# 15.net
KiCad netlist of a schematic drawn in EAGLE
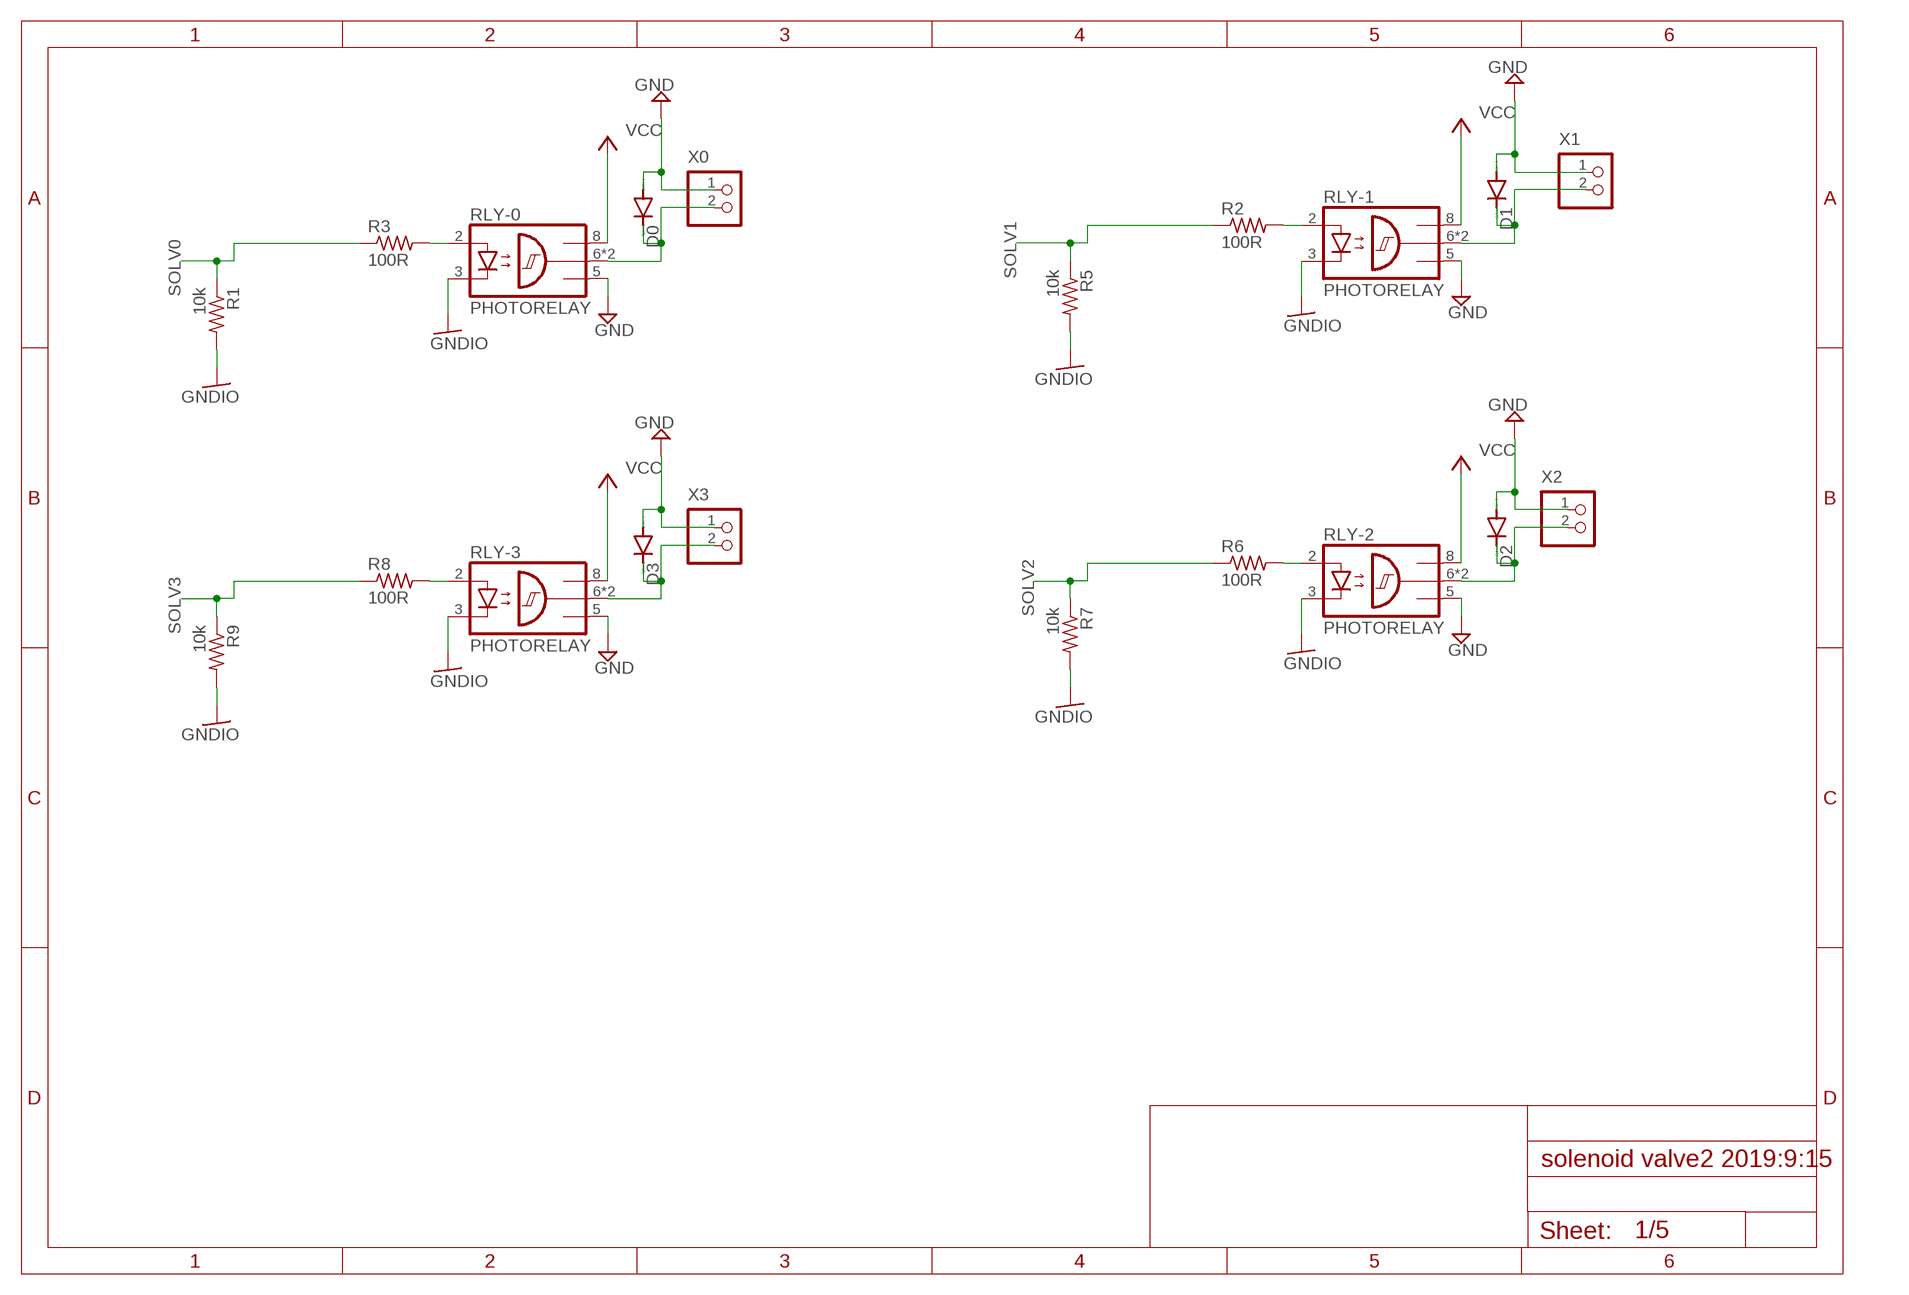
[diagram p0: schematic, sheet 1]
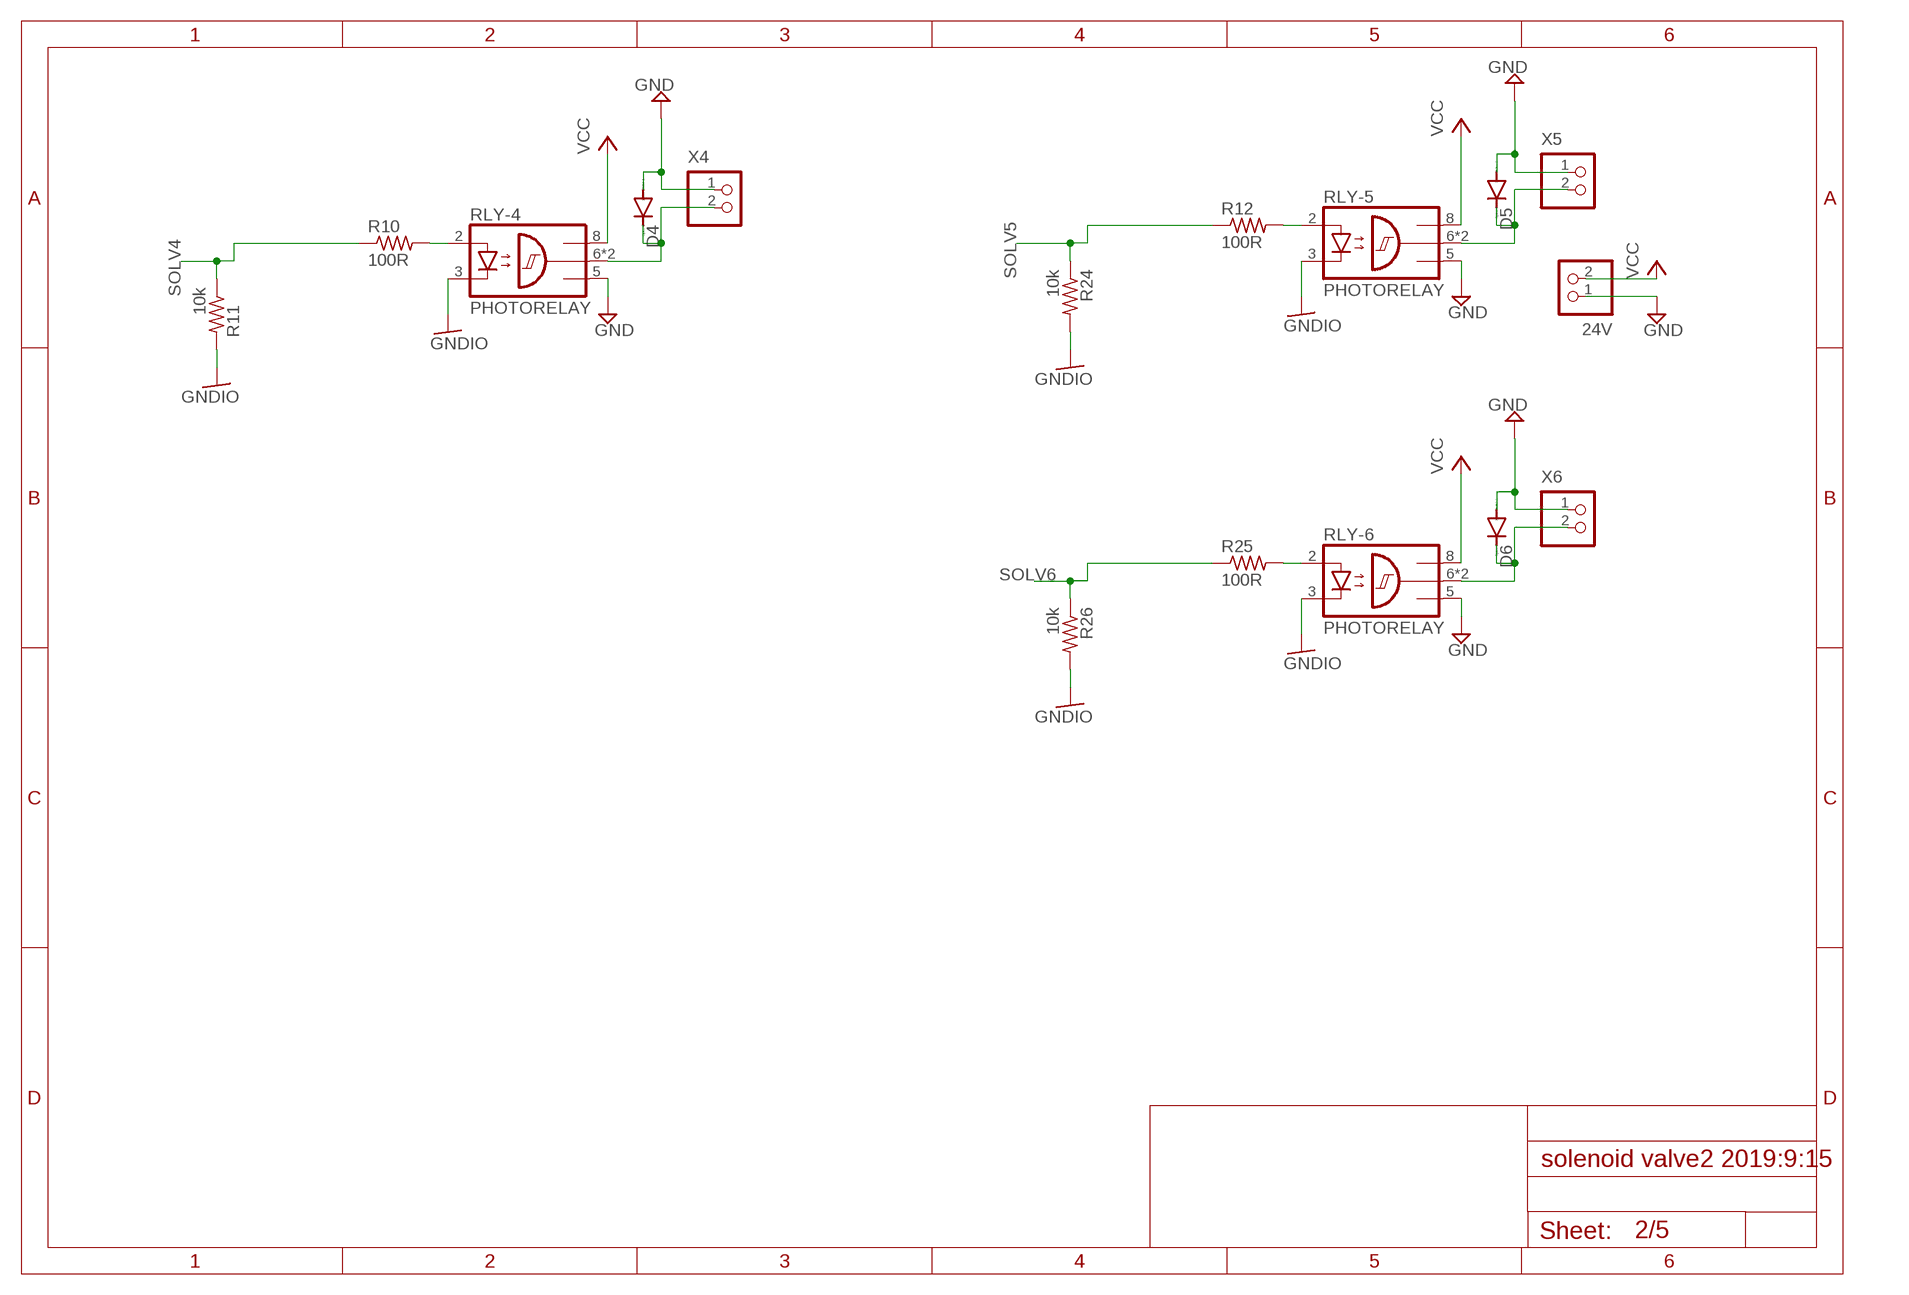
[diagram p1: schematic, sheet 2]
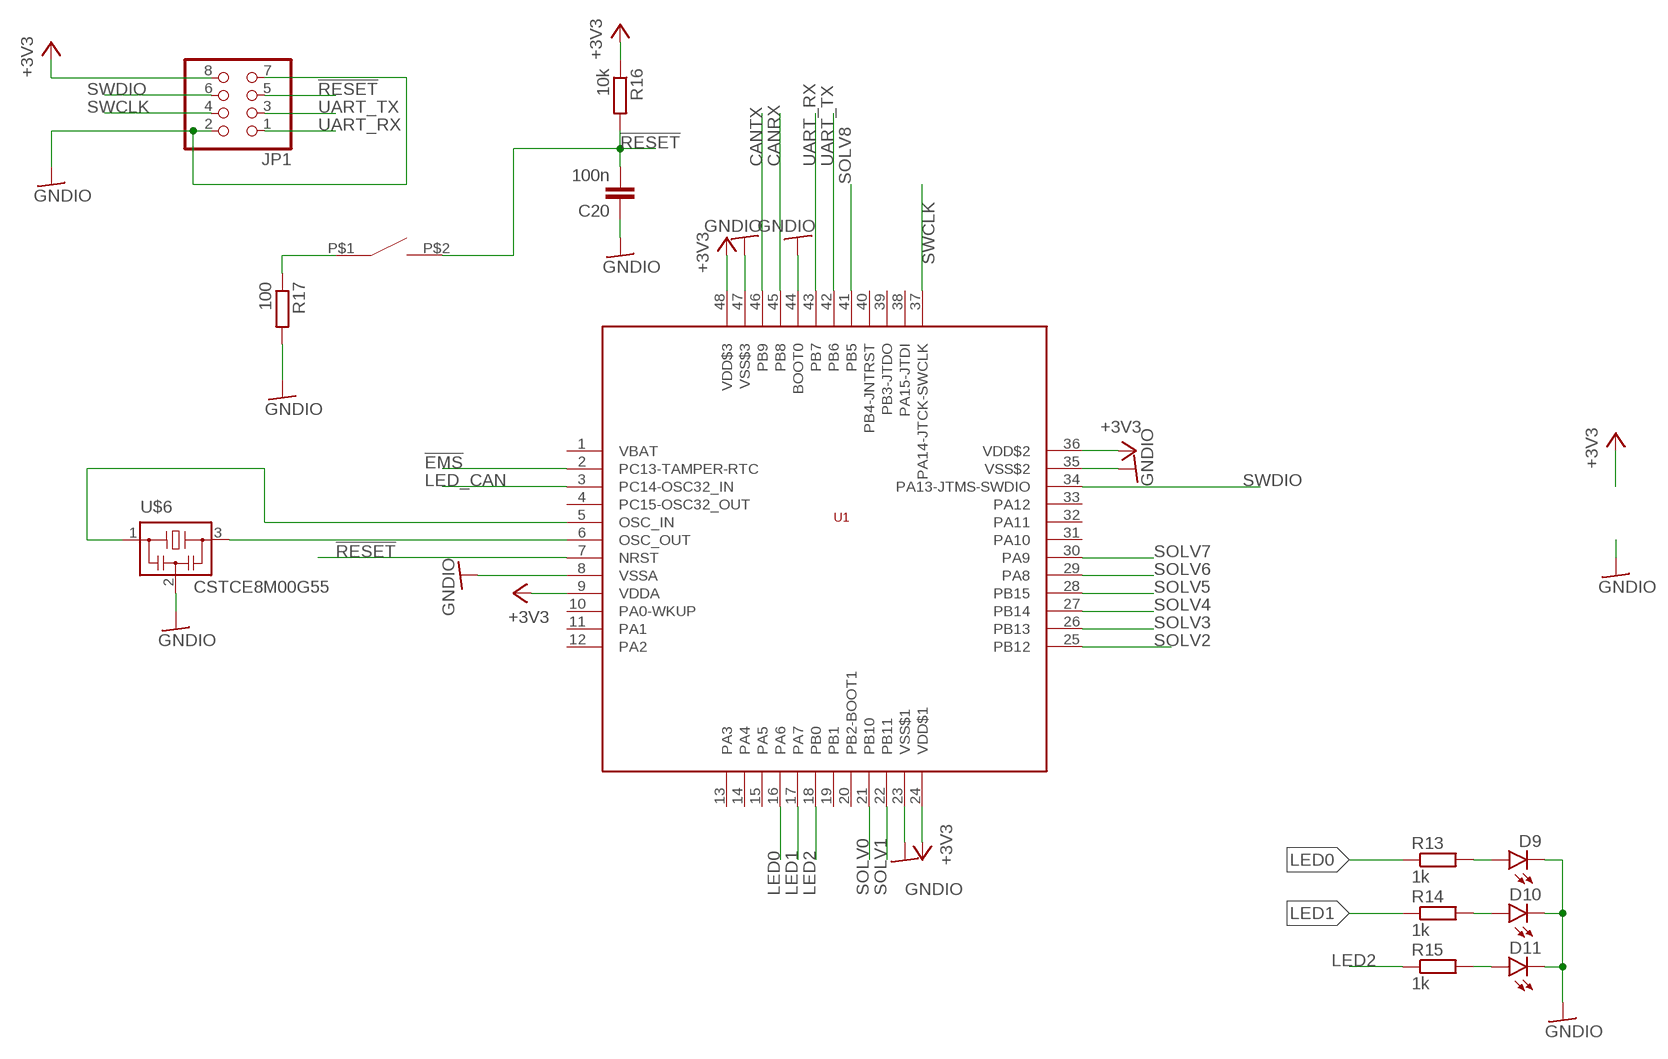
[diagram p2: schematic, sheet 3]
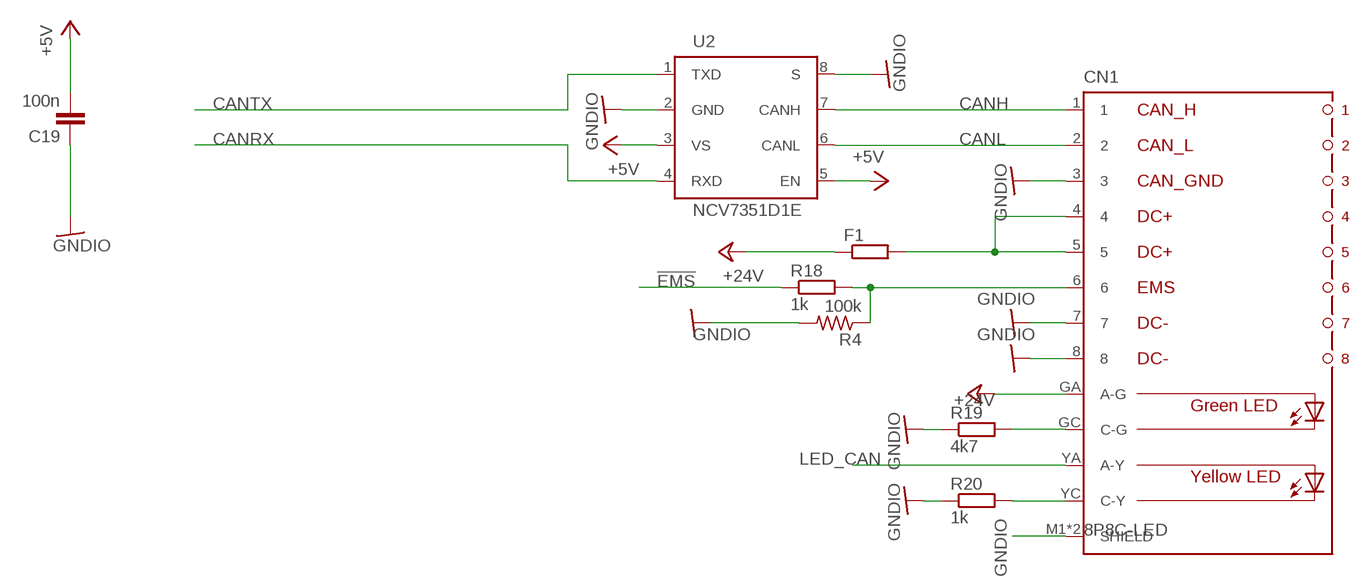
[diagram p3: schematic, sheet 4]
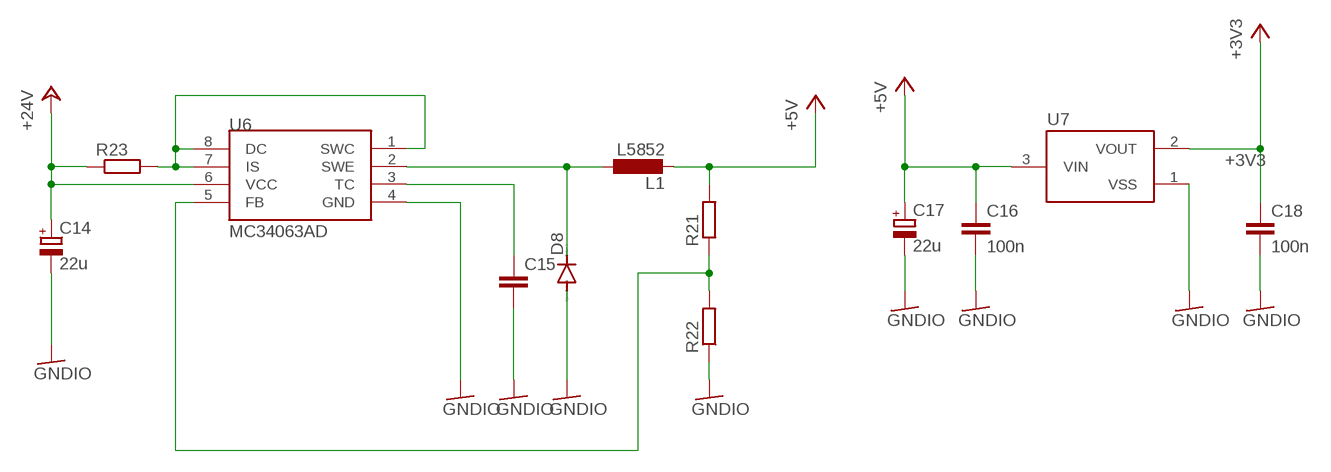
[diagram p4: schematic, sheet 5]

(export (version "E")
  (design (tool "Eeschema 10.0.6"))
  (components
    (comp (ref "C19")
      (value "100n")
      (footprint "eagle-import:C0603")
      (libsource (lib "eagle-import") (part "C-EUC0603"))
    )
    (comp (ref "CN1")
      (value "8P8C-LED")
      (footprint "eagle-import:8P8C-LED")
      (libsource (lib "eagle-import") (part "8P8C-LED"))
    )
    (comp (ref "F1")
      (value "R-EU_R1206")
      (footprint "eagle-import:R1206")
      (libsource (lib "eagle-import") (part "rcl_334_R-EU_R1206"))
    )
    (comp (ref "R4")
      (value "100k")
      (footprint "eagle-import:R0603")
      (libsource (lib "eagle-import") (part "R-US_R0603"))
    )
    (comp (ref "R18")
      (value "1k")
      (footprint "eagle-import:R0603")
      (libsource (lib "eagle-import") (part "rcl_334_R-EU_R0603"))
    )
    (comp (ref "R19")
      (value "4k7")
      (footprint "eagle-import:R0603")
      (libsource (lib "eagle-import") (part "rcl_334_R-EU_R0603"))
    )
    (comp (ref "R20")
      (value "1k")
      (footprint "eagle-import:R0603")
      (libsource (lib "eagle-import") (part "rcl_334_R-EU_R0603"))
    )
    (comp (ref "U2")
      (value "NCV7351D1E")
      (footprint "eagle-import:SO08")
      (libsource (lib "eagle-import") (part "NCV7351D1E"))
    )
    (comp (ref "C14")
      (value "22u")
      (footprint "eagle-import:E2-5")
      (libsource (lib "eagle-import") (part "CPOL-EUE2-5"))
    )
    (comp (ref "C15")
      (value "C-EUC0603")
      (footprint "eagle-import:C0603")
      (libsource (lib "eagle-import") (part "rcl_334_C-EUC0603"))
    )
    (comp (ref "C16")
      (value "100n")
      (footprint "eagle-import:C0603")
      (libsource (lib "eagle-import") (part "C-EUC0603"))
    )
    (comp (ref "C17")
      (value "22u")
      (footprint "eagle-import:E2-5")
      (libsource (lib "eagle-import") (part "CPOL-EUE2-5"))
    )
    (comp (ref "C18")
      (value "100n")
      (footprint "eagle-import:C0603")
      (libsource (lib "eagle-import") (part "C-EUC0603"))
    )
    (comp (ref "D8")
      (value "DIODE-SOD123")
      (footprint "eagle-import:SOD123")
      (libsource (lib "eagle-import") (part "DIODE-SOD123"))
    )
    (comp (ref "L1")
      (value "L5852")
      (footprint "eagle-import:L5852")
      (libsource (lib "eagle-import") (part "L5852"))
    )
    (comp (ref "R21")
      (value "R-EU_R0603")
      (footprint "eagle-import:R0603")
      (libsource (lib "eagle-import") (part "rcl_334_R-EU_R0603"))
    )
    (comp (ref "R22")
      (value "R-EU_R0603")
      (footprint "eagle-import:R0603")
      (libsource (lib "eagle-import") (part "rcl_334_R-EU_R0603"))
    )
    (comp (ref "R23")
      (value "R-EU_R1206")
      (footprint "eagle-import:R1206")
      (libsource (lib "eagle-import") (part "rcl_334_R-EU_R1206"))
    )
    (comp (ref "U6")
      (value "MC34063AD")
      (footprint "eagle-import:SOIC8")
      (libsource (lib "eagle-import") (part "MC34063AD"))
    )
    (comp (ref "U7")
      (value "XC6206")
      (footprint "eagle-import:SOT95P240X110-3")
      (libsource (lib "eagle-import") (part "XC6206"))
    )
    (comp (ref "D0")
      (value "DIODE-SOD123")
      (footprint "eagle-import:SOD123")
      (libsource (lib "eagle-import") (part "DIODE-SOD123"))
    )
    (comp (ref "D1")
      (value "DIODE-SOD123")
      (footprint "eagle-import:SOD123")
      (libsource (lib "eagle-import") (part "DIODE-SOD123"))
    )
    (comp (ref "D2")
      (value "DIODE-SOD123")
      (footprint "eagle-import:SOD123")
      (libsource (lib "eagle-import") (part "DIODE-SOD123"))
    )
    (comp (ref "D3")
      (value "DIODE-SOD123")
      (footprint "eagle-import:SOD123")
      (libsource (lib "eagle-import") (part "DIODE-SOD123"))
    )
    (comp (ref "R1")
      (value "10k")
      (footprint "eagle-import:R0603")
      (libsource (lib "eagle-import") (part "R-US_R0603"))
    )
    (comp (ref "R2")
      (value "100R")
      (footprint "eagle-import:R0603")
      (libsource (lib "eagle-import") (part "R-US_R0603"))
    )
    (comp (ref "R3")
      (value "100R")
      (footprint "eagle-import:R0603")
      (libsource (lib "eagle-import") (part "R-US_R0603"))
    )
    (comp (ref "R5")
      (value "10k")
      (footprint "eagle-import:R0603")
      (libsource (lib "eagle-import") (part "R-US_R0603"))
    )
    (comp (ref "R6")
      (value "100R")
      (footprint "eagle-import:R0603")
      (libsource (lib "eagle-import") (part "R-US_R0603"))
    )
    (comp (ref "R7")
      (value "10k")
      (footprint "eagle-import:R0603")
      (libsource (lib "eagle-import") (part "R-US_R0603"))
    )
    (comp (ref "R8")
      (value "100R")
      (footprint "eagle-import:R0603")
      (libsource (lib "eagle-import") (part "R-US_R0603"))
    )
    (comp (ref "R9")
      (value "10k")
      (footprint "eagle-import:R0603")
      (libsource (lib "eagle-import") (part "R-US_R0603"))
    )
    (comp (ref "RLY-0")
      (value "PHOTORELAY")
      (footprint "eagle-import:SOP254P1016X385-8")
      (libsource (lib "eagle-import") (part "PHOTORELAY"))
    )
    (comp (ref "RLY-1")
      (value "PHOTORELAY")
      (footprint "eagle-import:SOP254P1016X385-8")
      (libsource (lib "eagle-import") (part "PHOTORELAY"))
    )
    (comp (ref "RLY-2")
      (value "PHOTORELAY")
      (footprint "eagle-import:SOP254P1016X385-8")
      (libsource (lib "eagle-import") (part "PHOTORELAY"))
    )
    (comp (ref "RLY-3")
      (value "PHOTORELAY")
      (footprint "eagle-import:SOP254P1016X385-8")
      (libsource (lib "eagle-import") (part "PHOTORELAY"))
    )
    (comp (ref "X0")
      (value "S2B-XASK-1")
      (footprint "eagle-import:S2B-XASK-1")
      (libsource (lib "eagle-import") (part "S2B-XASK-1"))
    )
    (comp (ref "X1")
      (value "S2B-XASK-1")
      (footprint "eagle-import:S2B-XASK-1")
      (libsource (lib "eagle-import") (part "S2B-XASK-1"))
    )
    (comp (ref "X2")
      (value "S2B-XASK-1")
      (footprint "eagle-import:S2B-XASK-1")
      (libsource (lib "eagle-import") (part "S2B-XASK-1"))
    )
    (comp (ref "X3")
      (value "S2B-XASK-1")
      (footprint "eagle-import:S2B-XASK-1")
      (libsource (lib "eagle-import") (part "S2B-XASK-1"))
    )
    (comp (ref "24V")
      (value "S2B-XASK-1")
      (footprint "eagle-import:S2B-XASK-1")
      (libsource (lib "eagle-import") (part "S2B-XASK-1"))
    )
    (comp (ref "D4")
      (value "DIODE-SOD123")
      (footprint "eagle-import:SOD123")
      (libsource (lib "eagle-import") (part "DIODE-SOD123"))
    )
    (comp (ref "D5")
      (value "DIODE-SOD123")
      (footprint "eagle-import:SOD123")
      (libsource (lib "eagle-import") (part "DIODE-SOD123"))
    )
    (comp (ref "D6")
      (value "DIODE-SOD123")
      (footprint "eagle-import:SOD123")
      (libsource (lib "eagle-import") (part "DIODE-SOD123"))
    )
    (comp (ref "R10")
      (value "100R")
      (footprint "eagle-import:R0603")
      (libsource (lib "eagle-import") (part "R-US_R0603"))
    )
    (comp (ref "R11")
      (value "10k")
      (footprint "eagle-import:R0603")
      (libsource (lib "eagle-import") (part "R-US_R0603"))
    )
    (comp (ref "R12")
      (value "100R")
      (footprint "eagle-import:R0603")
      (libsource (lib "eagle-import") (part "R-US_R0603"))
    )
    (comp (ref "R24")
      (value "10k")
      (footprint "eagle-import:R0603")
      (libsource (lib "eagle-import") (part "R-US_R0603"))
    )
    (comp (ref "R25")
      (value "100R")
      (footprint "eagle-import:R0603")
      (libsource (lib "eagle-import") (part "R-US_R0603"))
    )
    (comp (ref "R26")
      (value "10k")
      (footprint "eagle-import:R0603")
      (libsource (lib "eagle-import") (part "R-US_R0603"))
    )
    (comp (ref "RLY-4")
      (value "PHOTORELAY")
      (footprint "eagle-import:SOP254P1016X385-8")
      (libsource (lib "eagle-import") (part "PHOTORELAY"))
    )
    (comp (ref "RLY-5")
      (value "PHOTORELAY")
      (footprint "eagle-import:SOP254P1016X385-8")
      (libsource (lib "eagle-import") (part "PHOTORELAY"))
    )
    (comp (ref "RLY-6")
      (value "PHOTORELAY")
      (footprint "eagle-import:SOP254P1016X385-8")
      (libsource (lib "eagle-import") (part "PHOTORELAY"))
    )
    (comp (ref "X4")
      (value "S2B-XASK-1")
      (footprint "eagle-import:S2B-XASK-1")
      (libsource (lib "eagle-import") (part "S2B-XASK-1"))
    )
    (comp (ref "X5")
      (value "S2B-XASK-1")
      (footprint "eagle-import:S2B-XASK-1")
      (libsource (lib "eagle-import") (part "S2B-XASK-1"))
    )
    (comp (ref "X6")
      (value "S2B-XASK-1")
      (footprint "eagle-import:S2B-XASK-1")
      (libsource (lib "eagle-import") (part "S2B-XASK-1"))
    )
    (comp (ref "C20")
      (value "100n")
      (footprint "eagle-import:C0603")
      (libsource (lib "eagle-import") (part "C-EUC0603"))
    )
    (comp (ref "D9")
      (value "LEDCHIPLED_0805")
      (footprint "eagle-import:CHIPLED_0805")
      (libsource (lib "eagle-import") (part "LEDCHIPLED_0805"))
    )
    (comp (ref "D10")
      (value "LEDCHIPLED_0805")
      (footprint "eagle-import:CHIPLED_0805")
      (libsource (lib "eagle-import") (part "LEDCHIPLED_0805"))
    )
    (comp (ref "D11")
      (value "LEDCHIPLED_0805")
      (footprint "eagle-import:CHIPLED_0805")
      (libsource (lib "eagle-import") (part "LEDCHIPLED_0805"))
    )
    (comp (ref "JP1")
      (value "PINHD-2X4/90")
      (footprint "eagle-import:2X04_90")
      (libsource (lib "eagle-import") (part "PINHD-2X4/90"))
    )
    (comp (ref "R13")
      (value "1k")
      (footprint "eagle-import:R0603")
      (libsource (lib "eagle-import") (part "R-EU_R0603"))
    )
    (comp (ref "R14")
      (value "1k")
      (footprint "eagle-import:R0603")
      (libsource (lib "eagle-import") (part "R-EU_R0603"))
    )
    (comp (ref "R15")
      (value "1k")
      (footprint "eagle-import:R0603")
      (libsource (lib "eagle-import") (part "R-EU_R0603"))
    )
    (comp (ref "R16")
      (value "10k")
      (footprint "eagle-import:R0603")
      (libsource (lib "eagle-import") (part "R-EU_R0603"))
    )
    (comp (ref "R17")
      (value "100")
      (footprint "eagle-import:R0603")
      (libsource (lib "eagle-import") (part "R-EU_R0603"))
    )
    (comp (ref "SW1")
      (value "SWITCH_TACTILETOP")
      (footprint "eagle-import:SWITCH_TACTILE_3X6")
      (libsource (lib "eagle-import") (part "SWITCH_TACTILETOP"))
    )
    (comp (ref "U$6")
      (value "CSTCE8M00G55")
      (footprint "eagle-import:CSTCE8M00G55")
      (libsource (lib "eagle-import") (part "CSTCE8M00G55"))
    )
    (comp (ref "U1")
      (value "STM32F103C8")
      (footprint "eagle-import:LQFP48")
      (libsource (lib "eagle-import") (part "STM32F103C8"))
    )
  )
  (nets
    (net (code "1") (name "+3V3") (class "Default")
      (node (ref "C18") (pin "1") (pinfunction "1_1") (pintype "passive"))
      (node (ref "JP1") (pin "8") (pinfunction "8_8") (pintype "passive"))
      (node (ref "R16") (pin "1") (pinfunction "1_1") (pintype "passive"))
      (node (ref "U1") (pin "24") (pinfunction "VDD$1_24") (pintype "passive"))
      (node (ref "U1") (pin "36") (pinfunction "VDD$2_36") (pintype "passive"))
      (node (ref "U1") (pin "48") (pinfunction "VDD$3_48") (pintype "passive"))
      (node (ref "U1") (pin "9") (pinfunction "VDDA_9") (pintype "bidirectional"))
      (node (ref "U7") (pin "2") (pinfunction "VOUT_2") (pintype "bidirectional"))
    )
    (net (code "2") (name "+5V") (class "Default")
      (node (ref "C16") (pin "1") (pinfunction "1_1") (pintype "passive"))
      (node (ref "C17") (pin "+") (pinfunction "+_+") (pintype "passive"))
      (node (ref "C19") (pin "2") (pinfunction "2_2") (pintype "passive"))
      (node (ref "L1") (pin "P$2") (pinfunction "2_P$2") (pintype "passive"))
      (node (ref "R21") (pin "2") (pinfunction "2_2") (pintype "passive"))
      (node (ref "U2") (pin "3") (pinfunction "VS_3") (pintype "power_in"))
      (node (ref "U2") (pin "5") (pinfunction "EN_5") (pintype "input"))
      (node (ref "U7") (pin "3") (pinfunction "VIN_3") (pintype "bidirectional"))
    )
    (net (code "3") (name "+24V") (class "Default")
      (node (ref "C14") (pin "+") (pinfunction "+_+") (pintype "passive"))
      (node (ref "CN1") (pin "GA") (pinfunction "A-G_GA") (pintype "passive"))
      (node (ref "F1") (pin "1") (pinfunction "1_1") (pintype "passive"))
      (node (ref "R23") (pin "1") (pinfunction "1_1") (pintype "passive"))
      (node (ref "U6") (pin "6") (pinfunction "VCC_6") (pintype "passive"))
    )
    (net (code "4") (name "CANH") (class "Default")
      (node (ref "CN1") (pin "1") (pinfunction "1_1") (pintype "input"))
      (node (ref "U2") (pin "7") (pinfunction "CANH_7") (pintype "output"))
    )
    (net (code "5") (name "CANL") (class "Default")
      (node (ref "CN1") (pin "2") (pinfunction "2_2") (pintype "input"))
      (node (ref "U2") (pin "6") (pinfunction "CANL_6") (pintype "output"))
    )
    (net (code "6") (name "CANRX") (class "Default")
      (node (ref "U1") (pin "45") (pinfunction "PB8_45") (pintype "bidirectional"))
      (node (ref "U2") (pin "4") (pinfunction "RXD_4") (pintype "output"))
    )
    (net (code "7") (name "CANTX") (class "Default")
      (node (ref "U1") (pin "46") (pinfunction "PB9_46") (pintype "bidirectional"))
      (node (ref "U2") (pin "1") (pinfunction "TXD_1") (pintype "input"))
    )
    (net (code "8") (name "GND") (class "Default")
      (node (ref "24V") (pin "1") (pinfunction "1_1") (pintype "passive"))
      (node (ref "D0") (pin "A") (pinfunction "A_A") (pintype "passive"))
      (node (ref "D1") (pin "A") (pinfunction "A_A") (pintype "passive"))
      (node (ref "D2") (pin "A") (pinfunction "A_A") (pintype "passive"))
      (node (ref "D3") (pin "A") (pinfunction "A_A") (pintype "passive"))
      (node (ref "D4") (pin "A") (pinfunction "A_A") (pintype "passive"))
      (node (ref "D5") (pin "A") (pinfunction "A_A") (pintype "passive"))
      (node (ref "D6") (pin "A") (pinfunction "A_A") (pintype "passive"))
      (node (ref "RLY-0") (pin "5") (pinfunction "GND_5") (pintype "passive"))
      (node (ref "RLY-1") (pin "5") (pinfunction "GND_5") (pintype "passive"))
      (node (ref "RLY-2") (pin "5") (pinfunction "GND_5") (pintype "passive"))
      (node (ref "RLY-3") (pin "5") (pinfunction "GND_5") (pintype "passive"))
      (node (ref "RLY-4") (pin "5") (pinfunction "GND_5") (pintype "passive"))
      (node (ref "RLY-5") (pin "5") (pinfunction "GND_5") (pintype "passive"))
      (node (ref "RLY-6") (pin "5") (pinfunction "GND_5") (pintype "passive"))
      (node (ref "X0") (pin "1") (pinfunction "1_1") (pintype "passive"))
      (node (ref "X1") (pin "1") (pinfunction "1_1") (pintype "passive"))
      (node (ref "X2") (pin "1") (pinfunction "1_1") (pintype "passive"))
      (node (ref "X3") (pin "1") (pinfunction "1_1") (pintype "passive"))
      (node (ref "X4") (pin "1") (pinfunction "1_1") (pintype "passive"))
      (node (ref "X5") (pin "1") (pinfunction "1_1") (pintype "passive"))
      (node (ref "X6") (pin "1") (pinfunction "1_1") (pintype "passive"))
    )
    (net (code "9") (name "GNDIO") (class "Default")
      (node (ref "C14") (pin "-") (pinfunction "-_-") (pintype "passive"))
      (node (ref "C15") (pin "2") (pinfunction "2_2") (pintype "passive"))
      (node (ref "C16") (pin "2") (pinfunction "2_2") (pintype "passive"))
      (node (ref "C17") (pin "-") (pinfunction "-_-") (pintype "passive"))
      (node (ref "C18") (pin "2") (pinfunction "2_2") (pintype "passive"))
      (node (ref "C19") (pin "1") (pinfunction "1_1") (pintype "passive"))
      (node (ref "C20") (pin "1") (pinfunction "1_1") (pintype "passive"))
      (node (ref "CN1") (pin "3") (pinfunction "3_3") (pintype "input"))
      (node (ref "CN1") (pin "7") (pinfunction "7_7") (pintype "input"))
      (node (ref "CN1") (pin "8") (pinfunction "8_8") (pintype "input"))
      (node (ref "CN1") (pin "M1") (pinfunction "SHIELD_M1") (pintype "passive"))
      (node (ref "CN1") (pin "M2") (pinfunction "SHIELD_M2") (pintype "passive"))
      (node (ref "D10") (pin "C") (pinfunction "C_C") (pintype "passive"))
      (node (ref "D11") (pin "C") (pinfunction "C_C") (pintype "passive"))
      (node (ref "D8") (pin "A") (pinfunction "A_A") (pintype "passive"))
      (node (ref "D9") (pin "C") (pinfunction "C_C") (pintype "passive"))
      (node (ref "JP1") (pin "2") (pinfunction "2_2") (pintype "passive"))
      (node (ref "JP1") (pin "7") (pinfunction "7_7") (pintype "passive"))
      (node (ref "R1") (pin "2") (pinfunction "2_2") (pintype "passive"))
      (node (ref "R11") (pin "2") (pinfunction "2_2") (pintype "passive"))
      (node (ref "R17") (pin "2") (pinfunction "2_2") (pintype "passive"))
      (node (ref "R19") (pin "1") (pinfunction "1_1") (pintype "passive"))
      (node (ref "R20") (pin "1") (pinfunction "1_1") (pintype "passive"))
      (node (ref "R22") (pin "1") (pinfunction "1_1") (pintype "passive"))
      (node (ref "R24") (pin "2") (pinfunction "2_2") (pintype "passive"))
      (node (ref "R26") (pin "2") (pinfunction "2_2") (pintype "passive"))
      (node (ref "R4") (pin "2") (pinfunction "2_2") (pintype "passive"))
      (node (ref "R5") (pin "2") (pinfunction "2_2") (pintype "passive"))
      (node (ref "R7") (pin "2") (pinfunction "2_2") (pintype "passive"))
      (node (ref "R9") (pin "2") (pinfunction "2_2") (pintype "passive"))
      (node (ref "RLY-0") (pin "3") (pinfunction "C_3") (pintype "passive"))
      (node (ref "RLY-1") (pin "3") (pinfunction "C_3") (pintype "passive"))
      (node (ref "RLY-2") (pin "3") (pinfunction "C_3") (pintype "passive"))
      (node (ref "RLY-3") (pin "3") (pinfunction "C_3") (pintype "passive"))
      (node (ref "RLY-4") (pin "3") (pinfunction "C_3") (pintype "passive"))
      (node (ref "RLY-5") (pin "3") (pinfunction "C_3") (pintype "passive"))
      (node (ref "RLY-6") (pin "3") (pinfunction "C_3") (pintype "passive"))
      (node (ref "U$6") (pin "2") (pinfunction "2_2") (pintype "passive"))
      (node (ref "U1") (pin "23") (pinfunction "VSS$1_23") (pintype "passive"))
      (node (ref "U1") (pin "35") (pinfunction "VSS$2_35") (pintype "passive"))
      (node (ref "U1") (pin "44") (pinfunction "BOOT0_44") (pintype "input"))
      (node (ref "U1") (pin "47") (pinfunction "VSS$3_47") (pintype "passive"))
      (node (ref "U1") (pin "8") (pinfunction "VSSA_8") (pintype "bidirectional"))
      (node (ref "U2") (pin "2") (pinfunction "GND_2") (pintype "power_in"))
      (node (ref "U2") (pin "8") (pinfunction "S_8") (pintype "input"))
      (node (ref "U6") (pin "4") (pinfunction "GND_4") (pintype "passive"))
      (node (ref "U7") (pin "1") (pinfunction "VSS_1") (pintype "bidirectional"))
    )
    (net (code "10") (name "LED0") (class "Default")
      (node (ref "R13") (pin "1") (pinfunction "1_1") (pintype "passive"))
      (node (ref "U1") (pin "16") (pinfunction "PA6_16") (pintype "bidirectional"))
    )
    (net (code "11") (name "LED1") (class "Default")
      (node (ref "R14") (pin "1") (pinfunction "1_1") (pintype "passive"))
      (node (ref "U1") (pin "17") (pinfunction "PA7_17") (pintype "bidirectional"))
    )
    (net (code "12") (name "LED2") (class "Default")
      (node (ref "R15") (pin "1") (pinfunction "1_1") (pintype "passive"))
      (node (ref "U1") (pin "18") (pinfunction "PB0_18") (pintype "bidirectional"))
    )
    (net (code "13") (name "LED_CAN") (class "Default")
      (node (ref "CN1") (pin "YA") (pinfunction "A-Y_YA") (pintype "passive"))
      (node (ref "U1") (pin "3") (pinfunction "PC14-OSC32_IN_3") (pintype "bidirectional"))
    )
    (net (code "14") (name "Net-(CN1-C-G)") (class "Default")
      (node (ref "CN1") (pin "GC") (pinfunction "C-G_GC") (pintype "passive"))
      (node (ref "R19") (pin "2") (pinfunction "2_2") (pintype "passive"))
    )
    (net (code "15") (name "Net-(CN1-C-Y)") (class "Default")
      (node (ref "CN1") (pin "YC") (pinfunction "C-Y_YC") (pintype "passive"))
      (node (ref "R20") (pin "2") (pinfunction "2_2") (pintype "passive"))
    )
    (net (code "16") (name "Net-(CN1-Pad4)") (class "Default")
      (node (ref "CN1") (pin "4") (pinfunction "4_4") (pintype "input"))
      (node (ref "CN1") (pin "5") (pinfunction "5_5") (pintype "input"))
      (node (ref "F1") (pin "2") (pinfunction "2_2") (pintype "passive"))
    )
    (net (code "17") (name "Net-(CN1-Pad6)") (class "Default")
      (node (ref "CN1") (pin "6") (pinfunction "6_6") (pintype "input"))
      (node (ref "R18") (pin "2") (pinfunction "2_2") (pintype "passive"))
      (node (ref "R4") (pin "1") (pinfunction "1_1") (pintype "passive"))
    )
    (net (code "18") (name "Net-(D0-PadC)") (class "Default")
      (node (ref "D0") (pin "C") (pinfunction "C_C") (pintype "passive"))
      (node (ref "RLY-0") (pin "6") (pinfunction "OUT_6") (pintype "passive"))
      (node (ref "RLY-0") (pin "7") (pinfunction "OUT_7") (pintype "passive"))
      (node (ref "X0") (pin "2") (pinfunction "2_2") (pintype "passive"))
    )
    (net (code "19") (name "Net-(D1-PadC)") (class "Default")
      (node (ref "D1") (pin "C") (pinfunction "C_C") (pintype "passive"))
      (node (ref "RLY-1") (pin "6") (pinfunction "OUT_6") (pintype "passive"))
      (node (ref "RLY-1") (pin "7") (pinfunction "OUT_7") (pintype "passive"))
      (node (ref "X1") (pin "2") (pinfunction "2_2") (pintype "passive"))
    )
    (net (code "20") (name "Net-(D2-PadC)") (class "Default")
      (node (ref "D2") (pin "C") (pinfunction "C_C") (pintype "passive"))
      (node (ref "RLY-2") (pin "6") (pinfunction "OUT_6") (pintype "passive"))
      (node (ref "RLY-2") (pin "7") (pinfunction "OUT_7") (pintype "passive"))
      (node (ref "X2") (pin "2") (pinfunction "2_2") (pintype "passive"))
    )
    (net (code "21") (name "Net-(D3-PadC)") (class "Default")
      (node (ref "D3") (pin "C") (pinfunction "C_C") (pintype "passive"))
      (node (ref "RLY-3") (pin "6") (pinfunction "OUT_6") (pintype "passive"))
      (node (ref "RLY-3") (pin "7") (pinfunction "OUT_7") (pintype "passive"))
      (node (ref "X3") (pin "2") (pinfunction "2_2") (pintype "passive"))
    )
    (net (code "22") (name "Net-(D4-PadC)") (class "Default")
      (node (ref "D4") (pin "C") (pinfunction "C_C") (pintype "passive"))
      (node (ref "RLY-4") (pin "6") (pinfunction "OUT_6") (pintype "passive"))
      (node (ref "RLY-4") (pin "7") (pinfunction "OUT_7") (pintype "passive"))
      (node (ref "X4") (pin "2") (pinfunction "2_2") (pintype "passive"))
    )
    (net (code "23") (name "Net-(D5-PadC)") (class "Default")
      (node (ref "D5") (pin "C") (pinfunction "C_C") (pintype "passive"))
      (node (ref "RLY-5") (pin "6") (pinfunction "OUT_6") (pintype "passive"))
      (node (ref "RLY-5") (pin "7") (pinfunction "OUT_7") (pintype "passive"))
      (node (ref "X5") (pin "2") (pinfunction "2_2") (pintype "passive"))
    )
    (net (code "24") (name "Net-(D6-PadC)") (class "Default")
      (node (ref "D6") (pin "C") (pinfunction "C_C") (pintype "passive"))
      (node (ref "RLY-6") (pin "6") (pinfunction "OUT_6") (pintype "passive"))
      (node (ref "RLY-6") (pin "7") (pinfunction "OUT_7") (pintype "passive"))
      (node (ref "X6") (pin "2") (pinfunction "2_2") (pintype "passive"))
    )
    (net (code "25") (name "Net-(D9-PadA)") (class "Default")
      (node (ref "D9") (pin "A") (pinfunction "A_A") (pintype "passive"))
      (node (ref "R13") (pin "2") (pinfunction "2_2") (pintype "passive"))
    )
    (net (code "26") (name "Net-(D10-PadA)") (class "Default")
      (node (ref "D10") (pin "A") (pinfunction "A_A") (pintype "passive"))
      (node (ref "R14") (pin "2") (pinfunction "2_2") (pintype "passive"))
    )
    (net (code "27") (name "Net-(D11-PadA)") (class "Default")
      (node (ref "D11") (pin "A") (pinfunction "A_A") (pintype "passive"))
      (node (ref "R15") (pin "2") (pinfunction "2_2") (pintype "passive"))
    )
    (net (code "28") (name "Net-(L1-1)") (class "Default")
      (node (ref "D8") (pin "C") (pinfunction "C_C") (pintype "passive"))
      (node (ref "L1") (pin "P$1") (pinfunction "1_P$1") (pintype "passive"))
      (node (ref "U6") (pin "2") (pinfunction "SWE_2") (pintype "passive"))
    )
    (net (code "29") (name "Net-(RLY-0-A)") (class "Default")
      (node (ref "R3") (pin "2") (pinfunction "2_2") (pintype "passive"))
      (node (ref "RLY-0") (pin "2") (pinfunction "A_2") (pintype "passive"))
    )
    (net (code "30") (name "Net-(RLY-1-A)") (class "Default")
      (node (ref "R2") (pin "2") (pinfunction "2_2") (pintype "passive"))
      (node (ref "RLY-1") (pin "2") (pinfunction "A_2") (pintype "passive"))
    )
    (net (code "31") (name "Net-(RLY-2-A)") (class "Default")
      (node (ref "R6") (pin "2") (pinfunction "2_2") (pintype "passive"))
      (node (ref "RLY-2") (pin "2") (pinfunction "A_2") (pintype "passive"))
    )
    (net (code "32") (name "Net-(RLY-3-A)") (class "Default")
      (node (ref "R8") (pin "2") (pinfunction "2_2") (pintype "passive"))
      (node (ref "RLY-3") (pin "2") (pinfunction "A_2") (pintype "passive"))
    )
    (net (code "33") (name "Net-(RLY-4-A)") (class "Default")
      (node (ref "R10") (pin "2") (pinfunction "2_2") (pintype "passive"))
      (node (ref "RLY-4") (pin "2") (pinfunction "A_2") (pintype "passive"))
    )
    (net (code "34") (name "Net-(RLY-5-A)") (class "Default")
      (node (ref "R12") (pin "2") (pinfunction "2_2") (pintype "passive"))
      (node (ref "RLY-5") (pin "2") (pinfunction "A_2") (pintype "passive"))
    )
    (net (code "35") (name "Net-(RLY-6-A)") (class "Default")
      (node (ref "R25") (pin "2") (pinfunction "2_2") (pintype "passive"))
      (node (ref "RLY-6") (pin "2") (pinfunction "A_2") (pintype "passive"))
    )
    (net (code "36") (name "Net-(SW1-1)") (class "Default")
      (node (ref "R17") (pin "1") (pinfunction "1_1") (pintype "passive"))
      (node (ref "SW1") (pin "P$1") (pinfunction "1_P$1") (pintype "bidirectional"))
    )
    (net (code "37") (name "Net-(U1-OSC_IN)") (class "Default")
      (node (ref "U$6") (pin "1") (pinfunction "1_1") (pintype "passive"))
      (node (ref "U1") (pin "5") (pinfunction "OSC_IN_5") (pintype "input"))
    )
    (net (code "38") (name "Net-(U1-OSC_OUT)") (class "Default")
      (node (ref "U$6") (pin "3") (pinfunction "3_3") (pintype "passive"))
      (node (ref "U1") (pin "6") (pinfunction "OSC_OUT_6") (pintype "output"))
    )
    (net (code "39") (name "Net-(U6-DC)") (class "Default")
      (node (ref "R23") (pin "2") (pinfunction "2_2") (pintype "passive"))
      (node (ref "U6") (pin "1") (pinfunction "SWC_1") (pintype "passive"))
      (node (ref "U6") (pin "7") (pinfunction "IS_7") (pintype "passive"))
      (node (ref "U6") (pin "8") (pinfunction "DC_8") (pintype "passive"))
    )
    (net (code "40") (name "Net-(U6-FB)") (class "Default")
      (node (ref "R21") (pin "1") (pinfunction "1_1") (pintype "passive"))
      (node (ref "R22") (pin "2") (pinfunction "2_2") (pintype "passive"))
      (node (ref "U6") (pin "5") (pinfunction "FB_5") (pintype "passive"))
    )
    (net (code "41") (name "Net-(U6-TC)") (class "Default")
      (node (ref "C15") (pin "1") (pinfunction "1_1") (pintype "passive"))
      (node (ref "U6") (pin "3") (pinfunction "TC_3") (pintype "passive"))
    )
    (net (code "42") (name "SOLV0") (class "Default")
      (node (ref "R1") (pin "1") (pinfunction "1_1") (pintype "passive"))
      (node (ref "R3") (pin "1") (pinfunction "1_1") (pintype "passive"))
      (node (ref "U1") (pin "21") (pinfunction "PB10_21") (pintype "bidirectional"))
    )
    (net (code "43") (name "SOLV1") (class "Default")
      (node (ref "R2") (pin "1") (pinfunction "1_1") (pintype "passive"))
      (node (ref "R5") (pin "1") (pinfunction "1_1") (pintype "passive"))
      (node (ref "U1") (pin "22") (pinfunction "PB11_22") (pintype "bidirectional"))
    )
    (net (code "44") (name "SOLV2") (class "Default")
      (node (ref "R6") (pin "1") (pinfunction "1_1") (pintype "passive"))
      (node (ref "R7") (pin "1") (pinfunction "1_1") (pintype "passive"))
      (node (ref "U1") (pin "25") (pinfunction "PB12_25") (pintype "bidirectional"))
    )
    (net (code "45") (name "SOLV3") (class "Default")
      (node (ref "R8") (pin "1") (pinfunction "1_1") (pintype "passive"))
      (node (ref "R9") (pin "1") (pinfunction "1_1") (pintype "passive"))
      (node (ref "U1") (pin "26") (pinfunction "PB13_26") (pintype "bidirectional"))
    )
    (net (code "46") (name "SOLV4") (class "Default")
      (node (ref "R10") (pin "1") (pinfunction "1_1") (pintype "passive"))
      (node (ref "R11") (pin "1") (pinfunction "1_1") (pintype "passive"))
      (node (ref "U1") (pin "27") (pinfunction "PB14_27") (pintype "bidirectional"))
    )
    (net (code "47") (name "SOLV5") (class "Default")
      (node (ref "R12") (pin "1") (pinfunction "1_1") (pintype "passive"))
      (node (ref "R24") (pin "1") (pinfunction "1_1") (pintype "passive"))
      (node (ref "U1") (pin "28") (pinfunction "PB15_28") (pintype "bidirectional"))
    )
    (net (code "48") (name "SOLV6") (class "Default")
      (node (ref "R25") (pin "1") (pinfunction "1_1") (pintype "passive"))
      (node (ref "R26") (pin "1") (pinfunction "1_1") (pintype "passive"))
      (node (ref "U1") (pin "29") (pinfunction "PA8_29") (pintype "bidirectional"))
    )
    (net (code "49") (name "SOLV7") (class "Default")
      (node (ref "U1") (pin "30") (pinfunction "PA9_30") (pintype "bidirectional"))
    )
    (net (code "50") (name "SOLV8") (class "Default")
      (node (ref "U1") (pin "41") (pinfunction "PB5_41") (pintype "bidirectional"))
    )
    (net (code "51") (name "SWCLK") (class "Default")
      (node (ref "JP1") (pin "4") (pinfunction "4_4") (pintype "passive"))
      (node (ref "U1") (pin "37") (pinfunction "PA14-JTCK-SWCLK_37") (pintype "bidirectional"))
    )
    (net (code "52") (name "SWDIO") (class "Default")
      (node (ref "JP1") (pin "6") (pinfunction "6_6") (pintype "passive"))
      (node (ref "U1") (pin "34") (pinfunction "PA13-JTMS-SWDIO_34") (pintype "bidirectional"))
    )
    (net (code "53") (name "UART_RX") (class "Default")
      (node (ref "JP1") (pin "1") (pinfunction "1_1") (pintype "passive"))
      (node (ref "U1") (pin "43") (pinfunction "PB7_43") (pintype "bidirectional"))
    )
    (net (code "54") (name "UART_TX") (class "Default")
      (node (ref "JP1") (pin "3") (pinfunction "3_3") (pintype "passive"))
      (node (ref "U1") (pin "42") (pinfunction "PB6_42") (pintype "bidirectional"))
    )
    (net (code "55") (name "VCC") (class "Default")
      (node (ref "24V") (pin "2") (pinfunction "2_2") (pintype "passive"))
      (node (ref "RLY-0") (pin "8") (pinfunction "VCC_8") (pintype "passive"))
      (node (ref "RLY-1") (pin "8") (pinfunction "VCC_8") (pintype "passive"))
      (node (ref "RLY-2") (pin "8") (pinfunction "VCC_8") (pintype "passive"))
      (node (ref "RLY-3") (pin "8") (pinfunction "VCC_8") (pintype "passive"))
      (node (ref "RLY-4") (pin "8") (pinfunction "VCC_8") (pintype "passive"))
      (node (ref "RLY-5") (pin "8") (pinfunction "VCC_8") (pintype "passive"))
      (node (ref "RLY-6") (pin "8") (pinfunction "VCC_8") (pintype "passive"))
    )
    (net (code "56") (name "unconnected-(U1-PA0-WKUP-Pad10)") (class "Default")
      (node (ref "U1") (pin "10") (pinfunction "PA0-WKUP_10") (pintype "bidirectional"))
    )
    (net (code "57") (name "unconnected-(U1-PA1-Pad11)") (class "Default")
      (node (ref "U1") (pin "11") (pinfunction "PA1_11") (pintype "bidirectional"))
    )
    (net (code "58") (name "unconnected-(U1-PA2-Pad12)") (class "Default")
      (node (ref "U1") (pin "12") (pinfunction "PA2_12") (pintype "bidirectional"))
    )
    (net (code "59") (name "unconnected-(U1-PA3-Pad13)") (class "Default")
      (node (ref "U1") (pin "13") (pinfunction "PA3_13") (pintype "bidirectional"))
    )
    (net (code "60") (name "unconnected-(U1-PA4-Pad14)") (class "Default")
      (node (ref "U1") (pin "14") (pinfunction "PA4_14") (pintype "bidirectional"))
    )
    (net (code "61") (name "unconnected-(U1-PA5-Pad15)") (class "Default")
      (node (ref "U1") (pin "15") (pinfunction "PA5_15") (pintype "bidirectional"))
    )
    (net (code "62") (name "unconnected-(U1-PA10-Pad31)") (class "Default")
      (node (ref "U1") (pin "31") (pinfunction "PA10_31") (pintype "bidirectional"))
    )
    (net (code "63") (name "unconnected-(U1-PA11-Pad32)") (class "Default")
      (node (ref "U1") (pin "32") (pinfunction "PA11_32") (pintype "bidirectional"))
    )
    (net (code "64") (name "unconnected-(U1-PA12-Pad33)") (class "Default")
      (node (ref "U1") (pin "33") (pinfunction "PA12_33") (pintype "bidirectional"))
    )
    (net (code "65") (name "unconnected-(U1-PA15-JTDI-Pad38)") (class "Default")
      (node (ref "U1") (pin "38") (pinfunction "PA15-JTDI_38") (pintype "bidirectional"))
    )
    (net (code "66") (name "unconnected-(U1-PB1-Pad19)") (class "Default")
      (node (ref "U1") (pin "19") (pinfunction "PB1_19") (pintype "bidirectional"))
    )
    (net (code "67") (name "unconnected-(U1-PB2-BOOT1-Pad20)") (class "Default")
      (node (ref "U1") (pin "20") (pinfunction "PB2-BOOT1_20") (pintype "bidirectional"))
    )
    (net (code "68") (name "unconnected-(U1-PB3-JTDO-Pad39)") (class "Default")
      (node (ref "U1") (pin "39") (pinfunction "PB3-JTDO_39") (pintype "bidirectional"))
    )
    (net (code "69") (name "unconnected-(U1-PB4-JNTRST-Pad40)") (class "Default")
      (node (ref "U1") (pin "40") (pinfunction "PB4-JNTRST_40") (pintype "bidirectional"))
    )
    (net (code "70") (name "unconnected-(U1-PC15-OSC32_OUT-Pad4)") (class "Default")
      (node (ref "U1") (pin "4") (pinfunction "PC15-OSC32_OUT_4") (pintype "bidirectional"))
    )
    (net (code "71") (name "unconnected-(U1-VBAT-Pad1)") (class "Default")
      (node (ref "U1") (pin "1") (pinfunction "VBAT_1") (pintype "passive"))
    )
    (net (code "72") (name "~{EMS}") (class "Default")
      (node (ref "R18") (pin "1") (pinfunction "1_1") (pintype "passive"))
      (node (ref "U1") (pin "2") (pinfunction "PC13-TAMPER-RTC_2") (pintype "bidirectional"))
    )
    (net (code "73") (name "~{RESET}") (class "Default")
      (node (ref "C20") (pin "2") (pinfunction "2_2") (pintype "passive"))
      (node (ref "JP1") (pin "5") (pinfunction "5_5") (pintype "passive"))
      (node (ref "R16") (pin "2") (pinfunction "2_2") (pintype "passive"))
      (node (ref "SW1") (pin "P$2") (pinfunction "2_P$2") (pintype "bidirectional"))
      (node (ref "U1") (pin "7") (pinfunction "NRST_7") (pintype "bidirectional"))
    )
  )
)
